# Tueroeffner.net
KiCad netlist of a schematic drawn in EAGLE
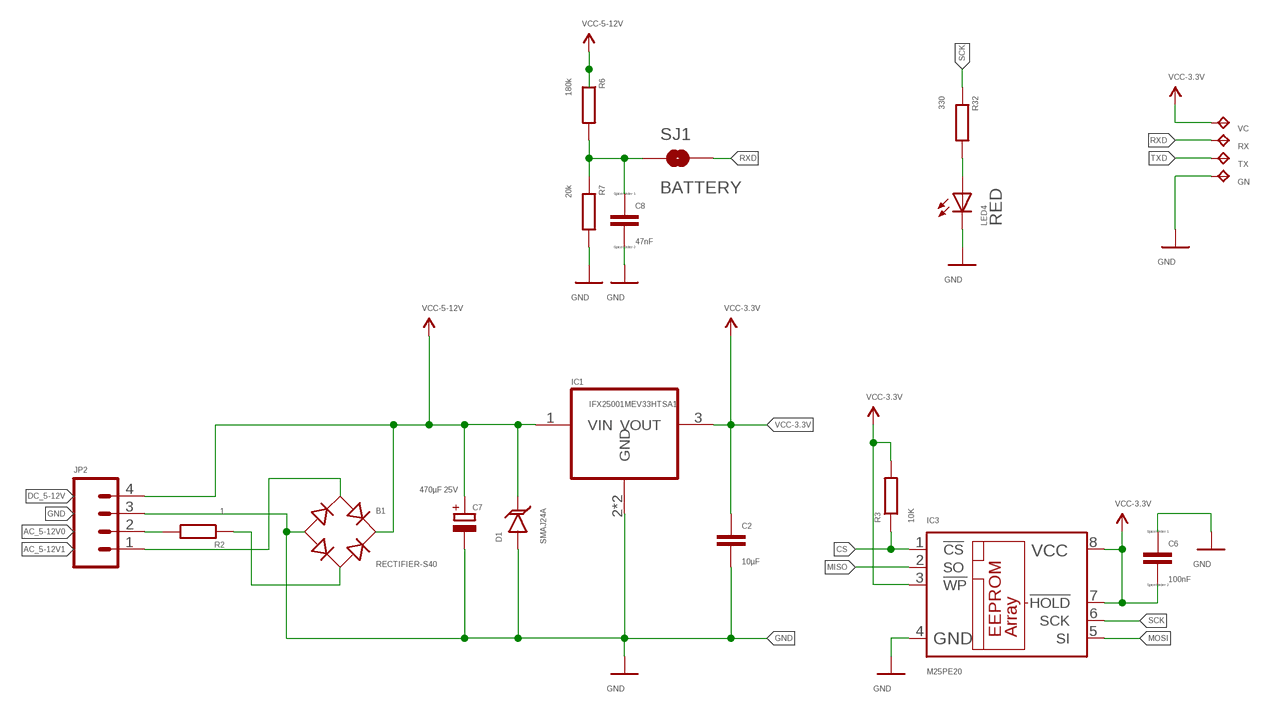
[diagram p0: schematic, sheet 1, part 1 of 2]
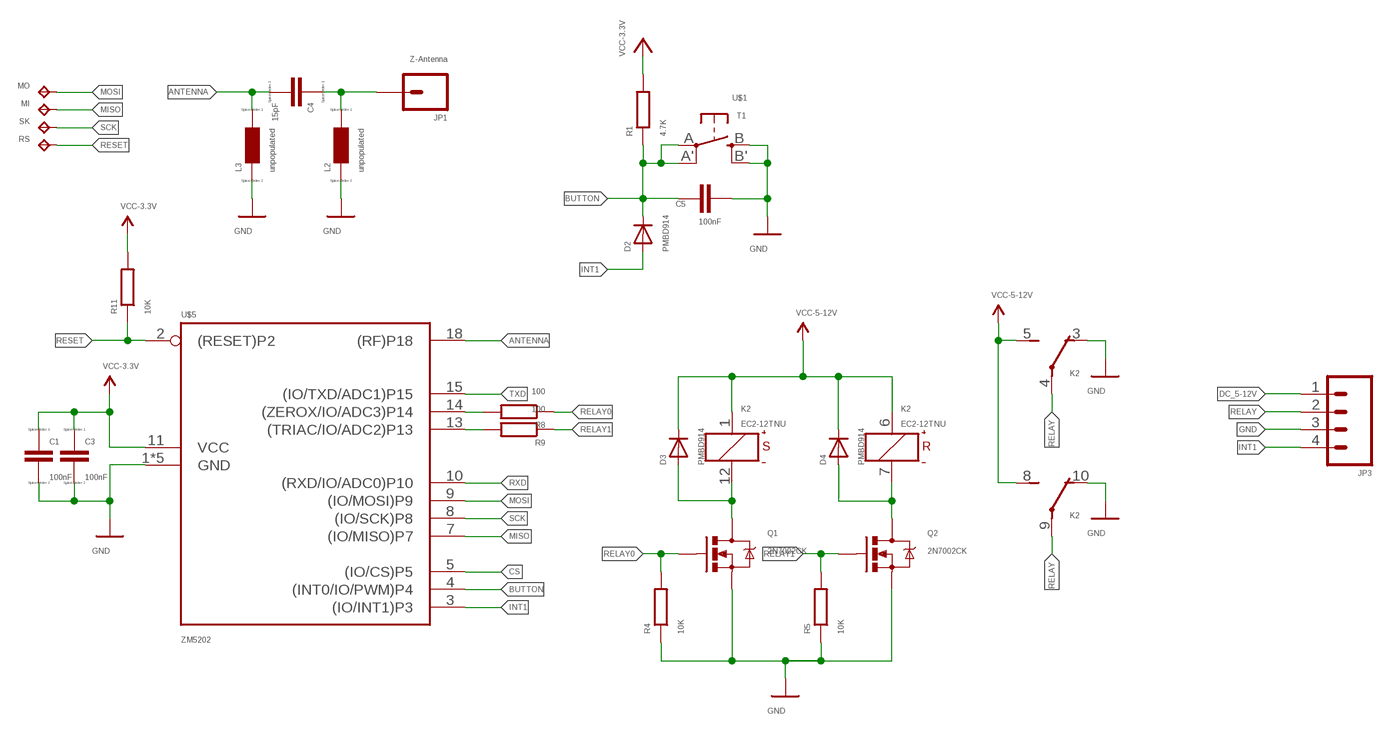
[diagram p1: schematic, sheet 1, part 2 of 2]

(export (version "E")
  (design (tool "Eeschema 10.0.6"))
  (components
    (comp (ref "B1")
      (value "RECTIFIER-S40")
      (footprint "eagle-import:TO-269AA")
      (libsource (lib "eagle-import") (part "RECTIFIER-S40"))
    )
    (comp (ref "C1")
      (value "100nF")
      (footprint "eagle-import:C2012")
      (libsource (lib "eagle-import") (part "CC2012"))
    )
    (comp (ref "C2")
      (value "10µF")
      (footprint "eagle-import:C0805")
      (libsource (lib "eagle-import") (part "C-EUC0805"))
    )
    (comp (ref "C3")
      (value "100nF")
      (footprint "eagle-import:C2012")
      (libsource (lib "eagle-import") (part "CC2012"))
    )
    (comp (ref "C4")
      (value "15pF")
      (footprint "eagle-import:C2012")
      (libsource (lib "eagle-import") (part "CC2012"))
    )
    (comp (ref "C5")
      (value "100nF")
      (footprint "eagle-import:C0805")
      (libsource (lib "eagle-import") (part "C-EUC0805"))
    )
    (comp (ref "C6")
      (value "100nF")
      (footprint "eagle-import:C2012")
      (libsource (lib "eagle-import") (part "CC2012"))
    )
    (comp (ref "C7")
      (value "470µF 25V")
      (footprint "eagle-import:175TMP-0810")
      (libsource (lib "eagle-import") (part "CPOL-EU175TMP-0810"))
    )
    (comp (ref "C8")
      (value "47nF")
      (footprint "eagle-import:C2012")
      (libsource (lib "eagle-import") (part "CC2012"))
    )
    (comp (ref "D1")
      (value "SMAJ24A")
      (footprint "eagle-import:SMA-DIODE")
      (libsource (lib "eagle-import") (part "TVSSMA"))
    )
    (comp (ref "D2")
      (value "PMBD914")
      (footprint "eagle-import:SOT23")
      (libsource (lib "eagle-import") (part "D-A1-C3"))
    )
    (comp (ref "D3")
      (value "PMBD914")
      (footprint "eagle-import:SOT23")
      (libsource (lib "eagle-import") (part "D-A1-C3"))
    )
    (comp (ref "D4")
      (value "PMBD914")
      (footprint "eagle-import:SOT23")
      (libsource (lib "eagle-import") (part "D-A1-C3"))
    )
    (comp (ref "GN")
      (value "TPTP14R")
      (footprint "eagle-import:TP14R")
      (libsource (lib "eagle-import") (part "TPTP14R"))
    )
    (comp (ref "IC1")
      (value "IFX25001MEV33HTSA1")
      (footprint "eagle-import:SOT223")
      (fields (field (name "MPN") "REG1118-2.85/2K5G4"))
      (libsource (lib "eagle-import") (part "REG1118"))
    )
    (comp (ref "IC3")
      (value "M25PE20")
      (footprint "eagle-import:SO-08")
      (fields (field (name "MPN") "25LC320A"))
      (libsource (lib "eagle-import") (part "25SNLC080"))
    )
    (comp (ref "JP1")
      (value "Z-Antenna")
      (footprint "eagle-import:1X01")
      (libsource (lib "eagle-import") (part "M01PTH"))
    )
    (comp (ref "JP2")
      (value "M04SCREW")
      (footprint "eagle-import:SCREWTERMINAL-3.5MM-4")
      (libsource (lib "eagle-import") (part "M04SCREW"))
    )
    (comp (ref "JP3")
      (value "M04SCREW")
      (footprint "eagle-import:SCREWTERMINAL-3.5MM-4")
      (libsource (lib "eagle-import") (part "M04SCREW"))
    )
    (comp (ref "K2")
      (value "EC2-12TNU")
      (footprint "eagle-import:TX2-L2")
      (fields (field (name "MF") "AROMAT/ MATSUSHITA") (field (name "MPN") "TX2-L2-12V"))
      (libsource (lib "eagle-import") (part "TX2?-L2-12V"))
    )
    (comp (ref "L2")
      (value "unpopulated")
      (footprint "eagle-import:L2012C")
      (libsource (lib "eagle-import") (part "LL2012C"))
    )
    (comp (ref "L3")
      (value "unpopulated")
      (footprint "eagle-import:L2012C")
      (libsource (lib "eagle-import") (part "LL2012C"))
    )
    (comp (ref "LED4")
      (value "RED")
      (footprint "eagle-import:CHIP-LED0805")
      (libsource (lib "eagle-import") (part "LEDCHIP-LED0805"))
    )
    (comp (ref "MI")
      (value "TPTP14R")
      (footprint "eagle-import:TP14R")
      (libsource (lib "eagle-import") (part "TPTP14R"))
    )
    (comp (ref "MO")
      (value "TPTP14R")
      (footprint "eagle-import:TP14R")
      (libsource (lib "eagle-import") (part "TPTP14R"))
    )
    (comp (ref "Q1")
      (value "2N7002CK")
      (footprint "eagle-import:SOT23-3")
      (libsource (lib "eagle-import") (part "MOSFET-NCHANNELBSS138"))
    )
    (comp (ref "Q2")
      (value "2N7002CK")
      (footprint "eagle-import:SOT23-3")
      (libsource (lib "eagle-import") (part "MOSFET-NCHANNELBSS138"))
    )
    (comp (ref "R1")
      (value "4.7K")
      (footprint "eagle-import:M0805")
      (libsource (lib "eagle-import") (part "R-EU_M0805"))
    )
    (comp (ref "R2")
      (value "1")
      (footprint "eagle-import:M2012")
      (libsource (lib "eagle-import") (part "resistor_R-EU_M2012"))
    )
    (comp (ref "R3")
      (value "10K")
      (footprint "eagle-import:M2012")
      (libsource (lib "eagle-import") (part "resistor_R-EU_M2012"))
    )
    (comp (ref "R4")
      (value "10K")
      (footprint "eagle-import:M2012")
      (libsource (lib "eagle-import") (part "resistor_R-EU_M2012"))
    )
    (comp (ref "R5")
      (value "10K")
      (footprint "eagle-import:M2012")
      (libsource (lib "eagle-import") (part "resistor_R-EU_M2012"))
    )
    (comp (ref "R6")
      (value "180k")
      (footprint "eagle-import:M2012")
      (libsource (lib "eagle-import") (part "resistor_R-EU_M2012"))
    )
    (comp (ref "R7")
      (value "20k")
      (footprint "eagle-import:M2012")
      (libsource (lib "eagle-import") (part "resistor_R-EU_M2012"))
    )
    (comp (ref "R8")
      (value "100")
      (footprint "eagle-import:M2012")
      (libsource (lib "eagle-import") (part "resistor_R-EU_M2012"))
    )
    (comp (ref "R9")
      (value "100")
      (footprint "eagle-import:M2012")
      (libsource (lib "eagle-import") (part "resistor_R-EU_M2012"))
    )
    (comp (ref "R11")
      (value "10K")
      (footprint "eagle-import:M2012")
      (libsource (lib "eagle-import") (part "resistor_R-EU_M2012"))
    )
    (comp (ref "R32")
      (value "330")
      (footprint "eagle-import:M2012")
      (libsource (lib "eagle-import") (part "resistor_R-EU_M2012"))
    )
    (comp (ref "RS")
      (value "TPTP14R")
      (footprint "eagle-import:TP14R")
      (libsource (lib "eagle-import") (part "TPTP14R"))
    )
    (comp (ref "RX")
      (value "TPTP14R")
      (footprint "eagle-import:TP14R")
      (libsource (lib "eagle-import") (part "TPTP14R"))
    )
    (comp (ref "SJ1")
      (value "BATTERY")
      (footprint "eagle-import:SJ_2S-TRACE")
      (libsource (lib "eagle-import") (part "SOLDERJUMPERTRACE"))
    )
    (comp (ref "SK")
      (value "TPTP14R")
      (footprint "eagle-import:TP14R")
      (libsource (lib "eagle-import") (part "TPTP14R"))
    )
    (comp (ref "TX")
      (value "TPTP14R")
      (footprint "eagle-import:TP14R")
      (libsource (lib "eagle-import") (part "TPTP14R"))
    )
    (comp (ref "U$1")
      (value "T1")
      (footprint "eagle-import:EVQ-Q2")
      (libsource (lib "eagle-import") (part "EVQQ2"))
    )
    (comp (ref "U$5")
      (value "ZM5202")
      (footprint "eagle-import:ZM5202_STERN")
      (libsource (lib "eagle-import") (part "ZM5202ZM5202_STERN"))
    )
    (comp (ref "VC")
      (value "TPTP14R")
      (footprint "eagle-import:TP14R")
      (libsource (lib "eagle-import") (part "TPTP14R"))
    )
  )
  (nets
    (net (code "1") (name "AC_5-12V0") (class "Default")
      (node (ref "JP2") (pin "2") (pinfunction "2_2") (pintype "passive"))
      (node (ref "R2") (pin "2") (pinfunction "2_2") (pintype "passive"))
    )
    (net (code "2") (name "AC_5-12V1") (class "Default")
      (node (ref "B1") (pin "AC1") (pinfunction "AC1_AC1") (pintype "passive"))
      (node (ref "JP2") (pin "1") (pinfunction "1_1") (pintype "passive"))
    )
    (net (code "3") (name "ANTENNA") (class "Default")
      (node (ref "C4") (pin "2") (pinfunction "2_2") (pintype "passive"))
      (node (ref "L3") (pin "1") (pinfunction "1_1") (pintype "passive"))
      (node (ref "U$5") (pin "18") (pinfunction "(RF)P18_18") (pintype "bidirectional"))
    )
    (net (code "4") (name "BUTTON") (class "Default")
      (node (ref "C5") (pin "1") (pinfunction "1_1") (pintype "passive"))
      (node (ref "D2") (pin "3") (pinfunction "C_3") (pintype "passive"))
      (node (ref "R1") (pin "1") (pinfunction "1_1") (pintype "passive"))
      (node (ref "U$1") (pin "A") (pinfunction "P_A") (pintype "passive"))
      (node (ref "U$1") (pin "A'") (pinfunction "P1_A'") (pintype "passive"))
      (node (ref "U$5") (pin "4") (pinfunction "(INT0/IO/PWM)P4_4") (pintype "bidirectional"))
    )
    (net (code "5") (name "CS") (class "Default")
      (node (ref "IC3") (pin "1") (pinfunction "~{CS}_1") (pintype "input"))
      (node (ref "R3") (pin "1") (pinfunction "1_1") (pintype "passive"))
      (node (ref "U$5") (pin "5") (pinfunction "(IO/CS)P5_5") (pintype "bidirectional"))
    )
    (net (code "6") (name "DC_5-12V") (class "Default")
      (node (ref "B1") (pin "+") (pinfunction "+_+") (pintype "passive"))
      (node (ref "C7") (pin "+") (pinfunction "+_+") (pintype "passive"))
      (node (ref "D1") (pin "C") (pinfunction "C_C") (pintype "passive"))
      (node (ref "D3") (pin "3") (pinfunction "C_3") (pintype "passive"))
      (node (ref "D4") (pin "3") (pinfunction "C_3") (pintype "passive"))
      (node (ref "IC1") (pin "1") (pinfunction "VIN_1") (pintype "input"))
      (node (ref "JP2") (pin "4") (pinfunction "4_4") (pintype "passive"))
      (node (ref "JP3") (pin "1") (pinfunction "1_1") (pintype "passive"))
      (node (ref "K2") (pin "1") (pinfunction "+_1") (pintype "passive"))
      (node (ref "K2") (pin "5") (pinfunction "S_5") (pintype "passive"))
      (node (ref "K2") (pin "6") (pinfunction "+_6") (pintype "passive"))
      (node (ref "K2") (pin "8") (pinfunction "S_8") (pintype "passive"))
      (node (ref "R6") (pin "1") (pinfunction "1_1") (pintype "passive"))
    )
    (net (code "7") (name "GND") (class "Default")
      (node (ref "B1") (pin "-") (pinfunction "-_-") (pintype "passive"))
      (node (ref "C1") (pin "2") (pinfunction "2_2") (pintype "passive"))
      (node (ref "C2") (pin "2") (pinfunction "2_2") (pintype "passive"))
      (node (ref "C3") (pin "2") (pinfunction "2_2") (pintype "passive"))
      (node (ref "C5") (pin "2") (pinfunction "2_2") (pintype "passive"))
      (node (ref "C6") (pin "1") (pinfunction "1_1") (pintype "passive"))
      (node (ref "C7") (pin "-") (pinfunction "-_-") (pintype "passive"))
      (node (ref "C8") (pin "2") (pinfunction "2_2") (pintype "passive"))
      (node (ref "D1") (pin "A") (pinfunction "A_A") (pintype "passive"))
      (node (ref "GN") (pin "TP") (pinfunction "TP_TP") (pintype "input"))
      (node (ref "IC1") (pin "2") (pinfunction "GND_2") (pintype "power_in"))
      (node (ref "IC1") (pin "4") (pinfunction "GND_4") (pintype "power_in"))
      (node (ref "IC3") (pin "4") (pinfunction "GND_4") (pintype "power_in"))
      (node (ref "JP2") (pin "3") (pinfunction "3_3") (pintype "passive"))
      (node (ref "JP3") (pin "3") (pinfunction "3_3") (pintype "passive"))
      (node (ref "K2") (pin "10") (pinfunction "O_10") (pintype "passive"))
      (node (ref "K2") (pin "3") (pinfunction "O_3") (pintype "passive"))
      (node (ref "L2") (pin "2") (pinfunction "2_2") (pintype "passive"))
      (node (ref "L3") (pin "2") (pinfunction "2_2") (pintype "passive"))
      (node (ref "LED4") (pin "C") (pinfunction "C_C") (pintype "passive"))
      (node (ref "Q1") (pin "2") (pinfunction "S_2") (pintype "passive"))
      (node (ref "Q2") (pin "2") (pinfunction "S_2") (pintype "passive"))
      (node (ref "R4") (pin "1") (pinfunction "1_1") (pintype "passive"))
      (node (ref "R5") (pin "1") (pinfunction "1_1") (pintype "passive"))
      (node (ref "R7") (pin "2") (pinfunction "2_2") (pintype "passive"))
      (node (ref "U$1") (pin "B") (pinfunction "S_B") (pintype "passive"))
      (node (ref "U$1") (pin "B'") (pinfunction "S1_B'") (pintype "passive"))
      (node (ref "U$5") (pin "1") (pinfunction "GND_1") (pintype "power_in"))
      (node (ref "U$5") (pin "12") (pinfunction "GND_12") (pintype "power_in"))
      (node (ref "U$5") (pin "16") (pinfunction "GND_16") (pintype "power_in"))
      (node (ref "U$5") (pin "17") (pinfunction "GND_17") (pintype "power_in"))
      (node (ref "U$5") (pin "6") (pinfunction "GND_6") (pintype "power_in"))
    )
    (net (code "8") (name "INT1") (class "Default")
      (node (ref "D2") (pin "1") (pinfunction "A_1") (pintype "passive"))
      (node (ref "JP3") (pin "4") (pinfunction "4_4") (pintype "passive"))
      (node (ref "U$5") (pin "3") (pinfunction "(IO/INT1)P3_3") (pintype "bidirectional"))
    )
    (net (code "9") (name "MISO") (class "Default")
      (node (ref "IC3") (pin "2") (pinfunction "SO_2") (pintype "bidirectional"))
      (node (ref "MI") (pin "TP") (pinfunction "TP_TP") (pintype "input"))
      (node (ref "U$5") (pin "7") (pinfunction "(IO/MISO)P7_7") (pintype "bidirectional"))
    )
    (net (code "10") (name "MOSI") (class "Default")
      (node (ref "IC3") (pin "5") (pinfunction "SI_5") (pintype "input"))
      (node (ref "MO") (pin "TP") (pinfunction "TP_TP") (pintype "input"))
      (node (ref "U$5") (pin "9") (pinfunction "(IO/MOSI)P9_9") (pintype "bidirectional"))
    )
    (net (code "11") (name "Net-(B1-PadAC2)") (class "Default")
      (node (ref "B1") (pin "AC2") (pinfunction "AC2_AC2") (pintype "passive"))
      (node (ref "R2") (pin "1") (pinfunction "1_1") (pintype "passive"))
    )
    (net (code "12") (name "Net-(C4-Pad1)") (class "Default")
      (node (ref "C4") (pin "1") (pinfunction "1_1") (pintype "passive"))
      (node (ref "JP1") (pin "1") (pinfunction "1_1") (pintype "passive"))
      (node (ref "L2") (pin "1") (pinfunction "1_1") (pintype "passive"))
    )
    (net (code "13") (name "Net-(C8-Pad1)") (class "Default")
      (node (ref "C8") (pin "1") (pinfunction "1_1") (pintype "passive"))
      (node (ref "R6") (pin "2") (pinfunction "2_2") (pintype "passive"))
      (node (ref "R7") (pin "1") (pinfunction "1_1") (pintype "passive"))
      (node (ref "SJ1") (pin "1") (pinfunction "1_1") (pintype "passive"))
    )
    (net (code "14") (name "Net-(D3-A)") (class "Default")
      (node (ref "D3") (pin "1") (pinfunction "A_1") (pintype "passive"))
      (node (ref "K2") (pin "12") (pinfunction "-_12") (pintype "passive"))
      (node (ref "Q1") (pin "3") (pinfunction "D_3") (pintype "passive"))
    )
    (net (code "15") (name "Net-(D4-A)") (class "Default")
      (node (ref "D4") (pin "1") (pinfunction "A_1") (pintype "passive"))
      (node (ref "K2") (pin "7") (pinfunction "-_7") (pintype "passive"))
      (node (ref "Q2") (pin "3") (pinfunction "D_3") (pintype "passive"))
    )
    (net (code "16") (name "Net-(LED4-PadA)") (class "Default")
      (node (ref "LED4") (pin "A") (pinfunction "A_A") (pintype "passive"))
      (node (ref "R32") (pin "2") (pinfunction "2_2") (pintype "passive"))
    )
    (net (code "17") (name "Net-(U$5-(TRIAC{slash}IO{slash}ADC2)P13)") (class "Default")
      (node (ref "R9") (pin "2") (pinfunction "2_2") (pintype "passive"))
      (node (ref "U$5") (pin "13") (pinfunction "(TRIAC/IO/ADC2)P13_13") (pintype "bidirectional"))
    )
    (net (code "18") (name "Net-(U$5-(ZEROX{slash}IO{slash}ADC3)P14)") (class "Default")
      (node (ref "R8") (pin "2") (pinfunction "2_2") (pintype "passive"))
      (node (ref "U$5") (pin "14") (pinfunction "(ZEROX/IO/ADC3)P14_14") (pintype "bidirectional"))
    )
    (net (code "19") (name "RELAY") (class "Default")
      (node (ref "JP3") (pin "2") (pinfunction "2_2") (pintype "passive"))
      (node (ref "K2") (pin "4") (pinfunction "P_4") (pintype "passive"))
      (node (ref "K2") (pin "9") (pinfunction "P_9") (pintype "passive"))
    )
    (net (code "20") (name "RELAY0") (class "Default")
      (node (ref "Q1") (pin "1") (pinfunction "G_1") (pintype "passive"))
      (node (ref "R4") (pin "2") (pinfunction "2_2") (pintype "passive"))
      (node (ref "R8") (pin "1") (pinfunction "1_1") (pintype "passive"))
    )
    (net (code "21") (name "RELAY1") (class "Default")
      (node (ref "Q2") (pin "1") (pinfunction "G_1") (pintype "passive"))
      (node (ref "R5") (pin "2") (pinfunction "2_2") (pintype "passive"))
      (node (ref "R9") (pin "1") (pinfunction "1_1") (pintype "passive"))
    )
    (net (code "22") (name "RESET") (class "Default")
      (node (ref "R11") (pin "1") (pinfunction "1_1") (pintype "passive"))
      (node (ref "RS") (pin "TP") (pinfunction "TP_TP") (pintype "input"))
      (node (ref "U$5") (pin "2") (pinfunction "(RESET)P2_2") (pintype "bidirectional"))
    )
    (net (code "23") (name "RXD") (class "Default")
      (node (ref "RX") (pin "TP") (pinfunction "TP_TP") (pintype "input"))
      (node (ref "SJ1") (pin "2") (pinfunction "2_2") (pintype "passive"))
      (node (ref "U$5") (pin "10") (pinfunction "(RXD/IO/ADC0)P10_10") (pintype "bidirectional"))
    )
    (net (code "24") (name "SCK") (class "Default")
      (node (ref "IC3") (pin "6") (pinfunction "SCK_6") (pintype "input"))
      (node (ref "R32") (pin "1") (pinfunction "1_1") (pintype "passive"))
      (node (ref "SK") (pin "TP") (pinfunction "TP_TP") (pintype "input"))
      (node (ref "U$5") (pin "8") (pinfunction "(IO/SCK)P8_8") (pintype "bidirectional"))
    )
    (net (code "25") (name "TXD") (class "Default")
      (node (ref "TX") (pin "TP") (pinfunction "TP_TP") (pintype "input"))
      (node (ref "U$5") (pin "15") (pinfunction "(IO/TXD/ADC1)P15_15") (pintype "bidirectional"))
    )
    (net (code "26") (name "VCC-3.3V") (class "Default")
      (node (ref "C1") (pin "1") (pinfunction "1_1") (pintype "passive"))
      (node (ref "C2") (pin "1") (pinfunction "1_1") (pintype "passive"))
      (node (ref "C3") (pin "1") (pinfunction "1_1") (pintype "passive"))
      (node (ref "C6") (pin "2") (pinfunction "2_2") (pintype "passive"))
      (node (ref "IC1") (pin "3") (pinfunction "VOUT_3") (pintype "output"))
      (node (ref "IC3") (pin "3") (pinfunction "~{WP}_3") (pintype "input"))
      (node (ref "IC3") (pin "7") (pinfunction "~{HOLD}_7") (pintype "input"))
      (node (ref "IC3") (pin "8") (pinfunction "VCC_8") (pintype "power_in"))
      (node (ref "R1") (pin "2") (pinfunction "2_2") (pintype "passive"))
      (node (ref "R11") (pin "2") (pinfunction "2_2") (pintype "passive"))
      (node (ref "R3") (pin "2") (pinfunction "2_2") (pintype "passive"))
      (node (ref "U$5") (pin "11") (pinfunction "VCC_11") (pintype "power_in"))
      (node (ref "VC") (pin "TP") (pinfunction "TP_TP") (pintype "input"))
    )
  )
)
